# SCH_RightHalf_2022-04-16.net
KiCad netlist of a schematic drawn in EasyEDA
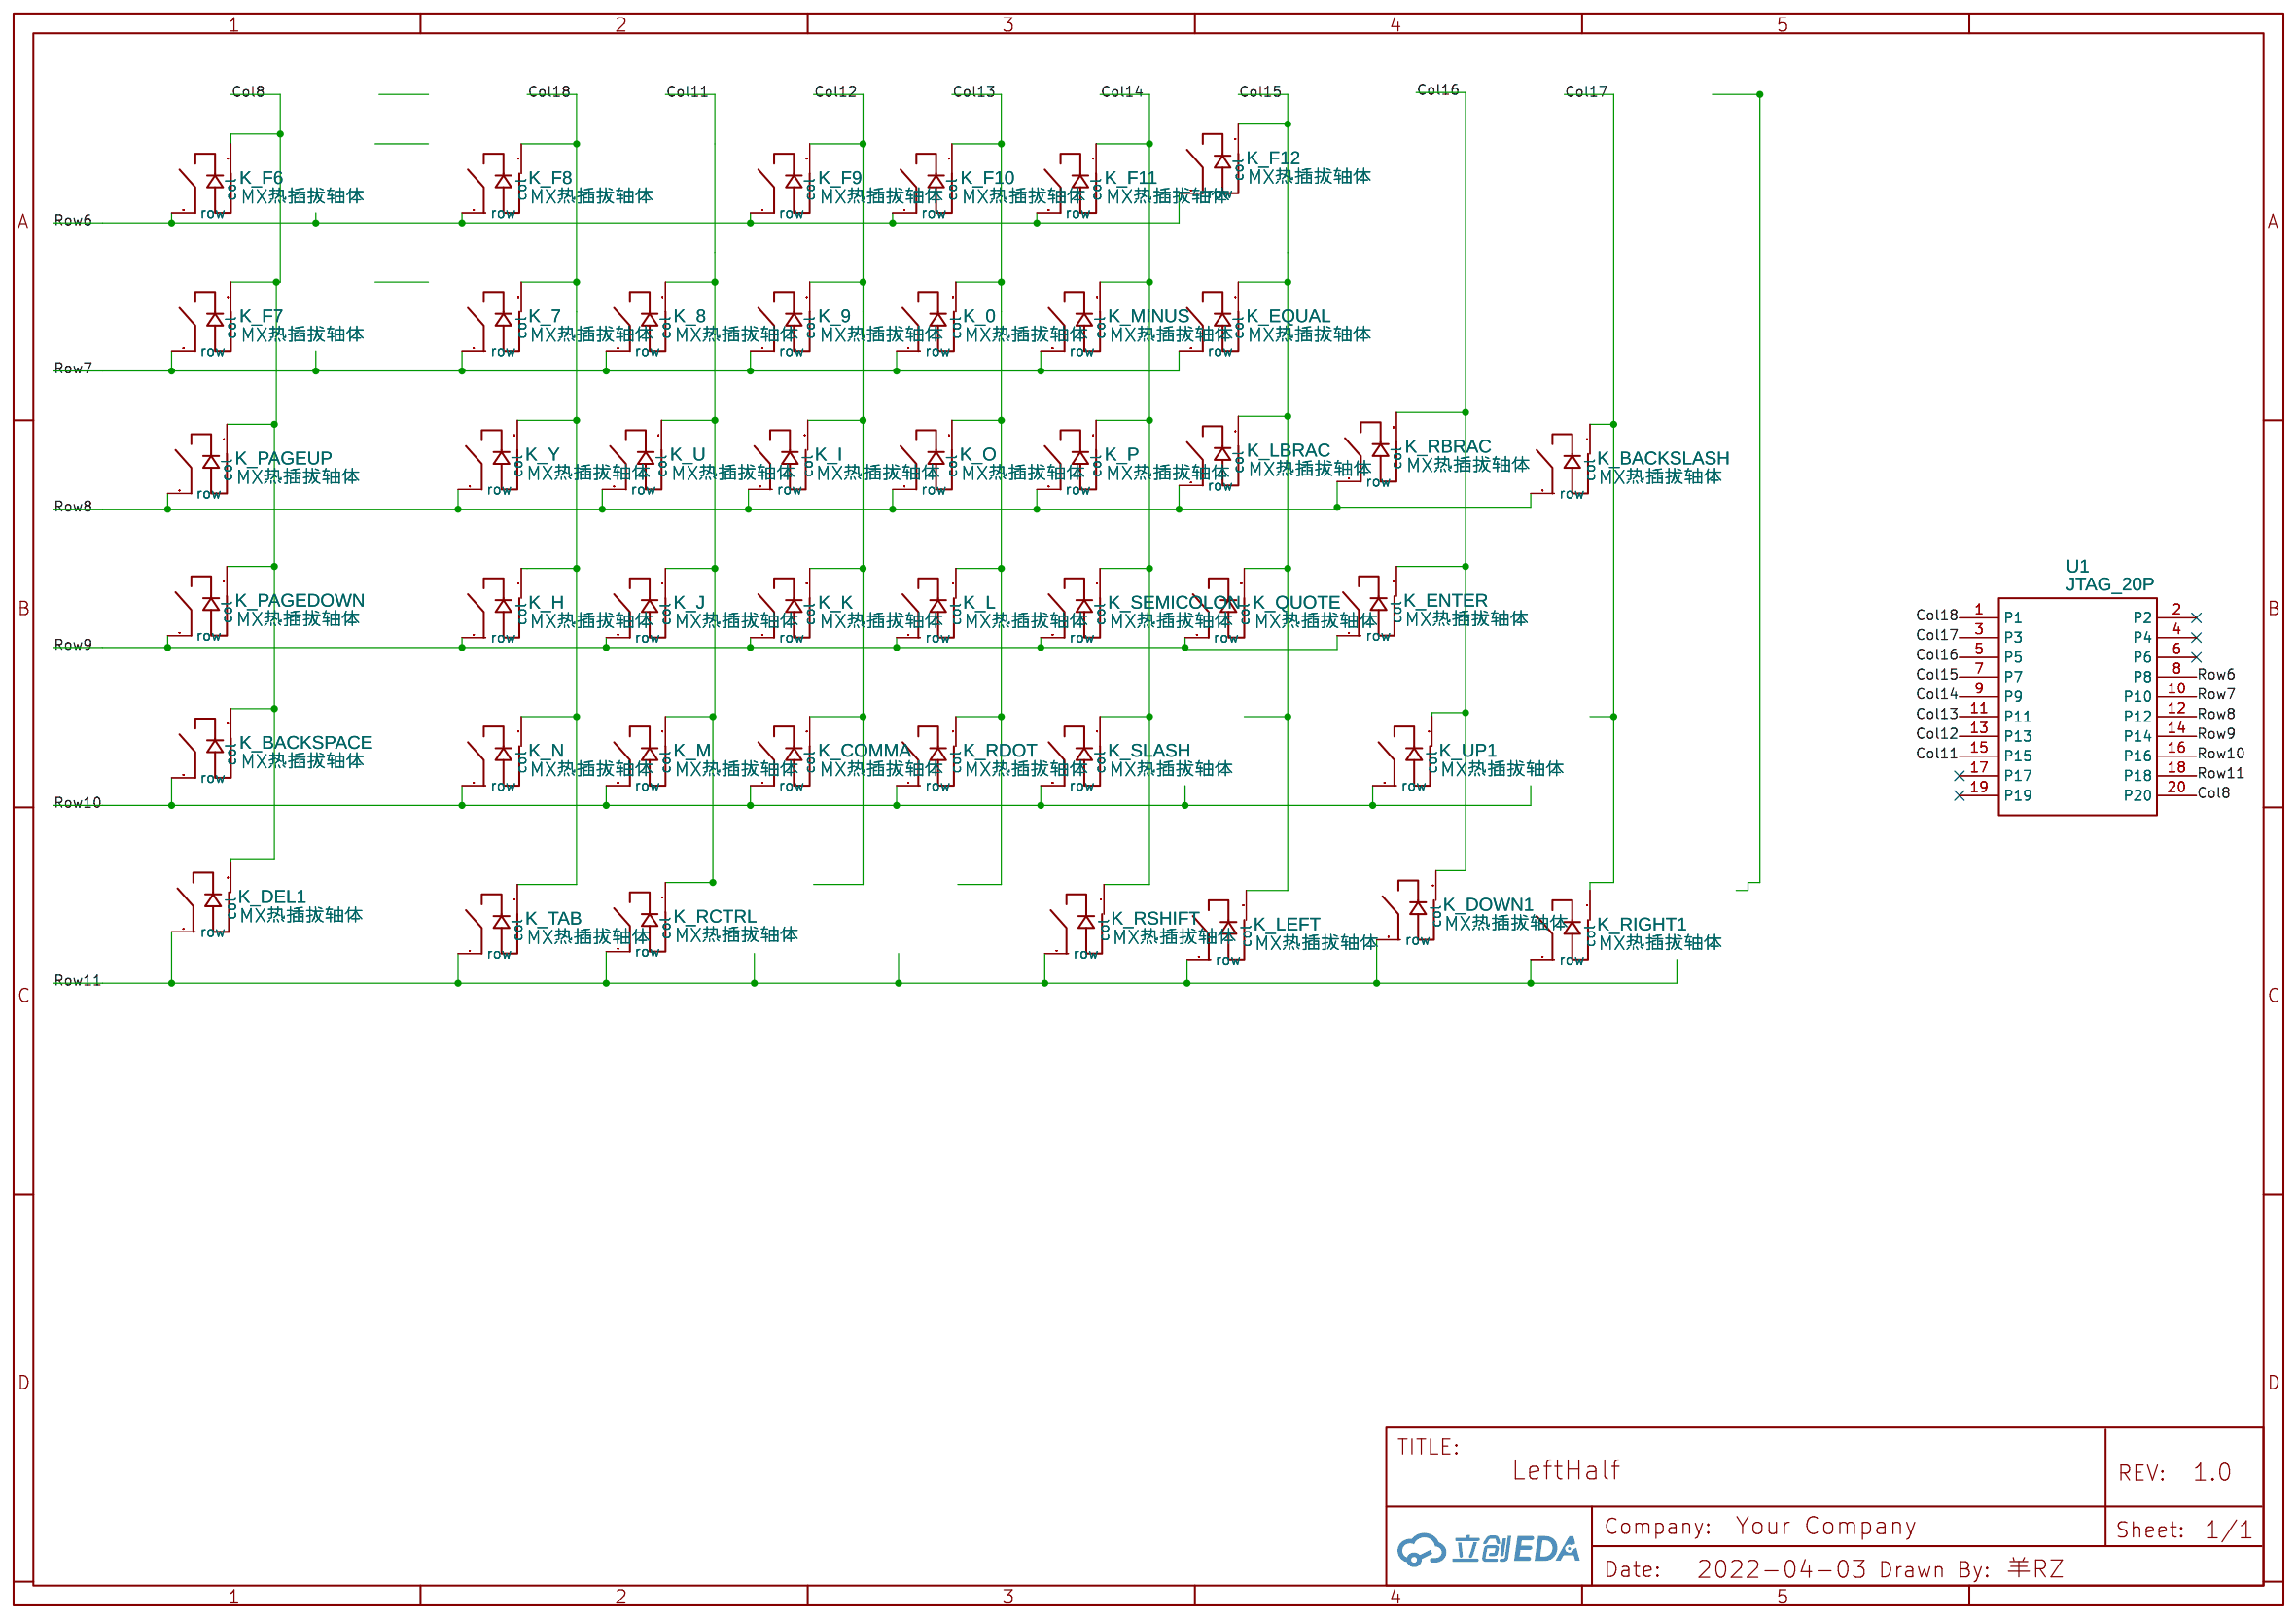
[diagram p0: schematic sheet]

(export (version "E")
  (design (tool "Eeschema 10.0.6"))
  (components
    (comp (ref "K_0") (value "MX热插拔轴体") (libsource (lib "") (part "MX热插拔轴体_19")))
    (comp (ref "K_7") (value "MX热插拔轴体") (libsource (lib "") (part "MX热插拔轴体_19")))
    (comp (ref "K_8") (value "MX热插拔轴体") (libsource (lib "") (part "MX热插拔轴体_2")))
    (comp (ref "K_9") (value "MX热插拔轴体") (libsource (lib "") (part "MX热插拔轴体_2")))
    (comp (ref "K_BACKSLASH") (value "MX热插拔轴体") (libsource (lib "") (part "MX热插拔轴体_10")))
    (comp (ref "K_BACKSPACE") (value "MX热插拔轴体") (libsource (lib "") (part "MX热插拔轴体_30")))
    (comp (ref "K_COMMA") (value "MX热插拔轴体") (libsource (lib "") (part "MX热插拔轴体_11")))
    (comp (ref "K_DEL1") (value "MX热插拔轴体") (libsource (lib "") (part "MX热插拔轴体_33")))
    (comp (ref "K_DOWN1") (value "MX热插拔轴体") (libsource (lib "") (part "MX热插拔轴体_32")))
    (comp (ref "K_ENTER") (value "MX热插拔轴体") (libsource (lib "") (part "MX热插拔轴体_26")))
    (comp (ref "K_EQUAL") (value "MX热插拔轴体") (libsource (lib "") (part "MX热插拔轴体_21")))
    (comp (ref "K_F6") (value "MX热插拔轴体") (libsource (lib "") (part "MX热插拔轴体_12")))
    (comp (ref "K_F7") (value "MX热插拔轴体") (libsource (lib "") (part "MX热插拔轴体_12")))
    (comp (ref "K_F8") (value "MX热插拔轴体") (libsource (lib "") (part "MX热插拔轴体_8")))
    (comp (ref "K_F9") (value "MX热插拔轴体") (libsource (lib "") (part "MX热插拔轴体_12")))
    (comp (ref "K_F10") (value "MX热插拔轴体") (libsource (lib "") (part "MX热插拔轴体_12")))
    (comp (ref "K_F11") (value "MX热插拔轴体") (libsource (lib "") (part "MX热插拔轴体_12")))
    (comp (ref "K_F12") (value "MX热插拔轴体") (libsource (lib "") (part "MX热插拔轴体_12")))
    (comp (ref "K_H") (value "MX热插拔轴体") (libsource (lib "") (part "MX热插拔轴体_27")))
    (comp (ref "K_I") (value "MX热插拔轴体") (libsource (lib "") (part "MX热插拔轴体_7")))
    (comp (ref "K_J") (value "MX热插拔轴体") (libsource (lib "") (part "MX热插拔轴体")))
    (comp (ref "K_K") (value "MX热插拔轴体") (libsource (lib "") (part "MX热插拔轴体_9")))
    (comp (ref "K_L") (value "MX热插拔轴体") (libsource (lib "") (part "MX热插拔轴体_35")))
    (comp (ref "K_LBRAC") (value "MX热插拔轴体") (libsource (lib "") (part "MX热插拔轴体_31")))
    (comp (ref "K_LEFT") (value "MX热插拔轴体") (libsource (lib "") (part "MX热插拔轴体_16")))
    (comp (ref "K_M") (value "MX热插拔轴体") (libsource (lib "") (part "MX热插拔轴体_34")))
    (comp (ref "K_MINUS") (value "MX热插拔轴体") (libsource (lib "") (part "MX热插拔轴体_25")))
    (comp (ref "K_N") (value "MX热插拔轴体") (libsource (lib "") (part "MX热插拔轴体_18")))
    (comp (ref "K_O") (value "MX热插拔轴体") (libsource (lib "") (part "MX热插拔轴体_36")))
    (comp (ref "K_P") (value "MX热插拔轴体") (libsource (lib "") (part "MX热插拔轴体_29")))
    (comp (ref "K_PAGEDOWN") (value "MX热插拔轴体") (libsource (lib "") (part "MX热插拔轴体_17")))
    (comp (ref "K_PAGEUP") (value "MX热插拔轴体") (libsource (lib "") (part "MX热插拔轴体_3")))
    (comp (ref "K_QUOTE") (value "MX热插拔轴体") (libsource (lib "") (part "MX热插拔轴体_22")))
    (comp (ref "K_RBRAC") (value "MX热插拔轴体") (libsource (lib "") (part "MX热插拔轴体_23")))
    (comp (ref "K_RCTRL") (value "MX热插拔轴体") (libsource (lib "") (part "MX热插拔轴体_14")))
    (comp (ref "K_RDOT") (value "MX热插拔轴体") (libsource (lib "") (part "MX热插拔轴体_20")))
    (comp (ref "K_RIGHT1") (value "MX热插拔轴体") (libsource (lib "") (part "MX热插拔轴体_4")))
    (comp (ref "K_RSHIFT") (value "MX热插拔轴体") (libsource (lib "") (part "MX热插拔轴体_5")))
    (comp (ref "K_SEMICOLON") (value "MX热插拔轴体") (libsource (lib "") (part "MX热插拔轴体_24")))
    (comp (ref "K_SLASH") (value "MX热插拔轴体") (libsource (lib "") (part "MX热插拔轴体_1")))
    (comp (ref "K_TAB") (value "MX热插拔轴体") (libsource (lib "") (part "MX热插拔轴体_6")))
    (comp (ref "K_U") (value "MX热插拔轴体") (libsource (lib "") (part "MX热插拔轴体_28")))
    (comp (ref "K_UP1") (value "MX热插拔轴体") (libsource (lib "") (part "MX热插拔轴体_15")))
    (comp (ref "K_Y") (value "MX热插拔轴体") (libsource (lib "") (part "MX热插拔轴体_13")))
    (comp (ref "U1") (value "JTAG_20P") (libsource (lib "") (part "JTAG_20P")))
  )
  (nets
    (net (code "1") (name "/Col8") (class "Default")
      (node (ref "K_BACKSPACE") (pin "COL") (pinfunction "col_COL") (pintype "unspecified"))
      (node (ref "K_DEL1") (pin "COL") (pinfunction "col_COL") (pintype "unspecified"))
      (node (ref "K_F6") (pin "COL") (pinfunction "col_COL") (pintype "unspecified"))
      (node (ref "K_F7") (pin "COL") (pinfunction "col_COL") (pintype "unspecified"))
      (node (ref "K_PAGEDOWN") (pin "COL") (pinfunction "col_COL") (pintype "unspecified"))
      (node (ref "K_PAGEUP") (pin "COL") (pinfunction "col_COL") (pintype "unspecified"))
      (node (ref "U1") (pin "20") (pinfunction "P20_20") (pintype "unspecified"))
    )
    (net (code "2") (name "/Col11") (class "Default")
      (node (ref "K_8") (pin "COL") (pinfunction "col_COL") (pintype "unspecified"))
      (node (ref "K_J") (pin "COL") (pinfunction "col_COL") (pintype "unspecified"))
      (node (ref "K_M") (pin "COL") (pinfunction "col_COL") (pintype "unspecified"))
      (node (ref "K_RCTRL") (pin "COL") (pinfunction "col_COL") (pintype "unspecified"))
      (node (ref "K_U") (pin "COL") (pinfunction "col_COL") (pintype "unspecified"))
      (node (ref "U1") (pin "15") (pinfunction "P15_15") (pintype "unspecified"))
    )
    (net (code "3") (name "/Col12") (class "Default")
      (node (ref "K_9") (pin "COL") (pinfunction "col_COL") (pintype "unspecified"))
      (node (ref "K_COMMA") (pin "COL") (pinfunction "col_COL") (pintype "unspecified"))
      (node (ref "K_F9") (pin "COL") (pinfunction "col_COL") (pintype "unspecified"))
      (node (ref "K_I") (pin "COL") (pinfunction "col_COL") (pintype "unspecified"))
      (node (ref "K_K") (pin "COL") (pinfunction "col_COL") (pintype "unspecified"))
      (node (ref "U1") (pin "13") (pinfunction "P13_13") (pintype "unspecified"))
    )
    (net (code "4") (name "/Col13") (class "Default")
      (node (ref "K_0") (pin "COL") (pinfunction "col_COL") (pintype "unspecified"))
      (node (ref "K_F10") (pin "COL") (pinfunction "col_COL") (pintype "unspecified"))
      (node (ref "K_L") (pin "COL") (pinfunction "col_COL") (pintype "unspecified"))
      (node (ref "K_O") (pin "COL") (pinfunction "col_COL") (pintype "unspecified"))
      (node (ref "K_RDOT") (pin "COL") (pinfunction "col_COL") (pintype "unspecified"))
      (node (ref "U1") (pin "11") (pinfunction "P11_11") (pintype "unspecified"))
    )
    (net (code "5") (name "/Col14") (class "Default")
      (node (ref "K_F11") (pin "COL") (pinfunction "col_COL") (pintype "unspecified"))
      (node (ref "K_MINUS") (pin "COL") (pinfunction "col_COL") (pintype "unspecified"))
      (node (ref "K_P") (pin "COL") (pinfunction "col_COL") (pintype "unspecified"))
      (node (ref "K_RSHIFT") (pin "COL") (pinfunction "col_COL") (pintype "unspecified"))
      (node (ref "K_SEMICOLON") (pin "COL") (pinfunction "col_COL") (pintype "unspecified"))
      (node (ref "K_SLASH") (pin "COL") (pinfunction "col_COL") (pintype "unspecified"))
      (node (ref "U1") (pin "9") (pinfunction "P9_9") (pintype "unspecified"))
    )
    (net (code "6") (name "/Col15") (class "Default")
      (node (ref "K_EQUAL") (pin "COL") (pinfunction "col_COL") (pintype "unspecified"))
      (node (ref "K_F12") (pin "COL") (pinfunction "col_COL") (pintype "unspecified"))
      (node (ref "K_LBRAC") (pin "COL") (pinfunction "col_COL") (pintype "unspecified"))
      (node (ref "K_LEFT") (pin "COL") (pinfunction "col_COL") (pintype "unspecified"))
      (node (ref "K_QUOTE") (pin "COL") (pinfunction "col_COL") (pintype "unspecified"))
      (node (ref "U1") (pin "7") (pinfunction "P7_7") (pintype "unspecified"))
    )
    (net (code "7") (name "/Col16") (class "Default")
      (node (ref "K_DOWN1") (pin "COL") (pinfunction "col_COL") (pintype "unspecified"))
      (node (ref "K_ENTER") (pin "COL") (pinfunction "col_COL") (pintype "unspecified"))
      (node (ref "K_RBRAC") (pin "COL") (pinfunction "col_COL") (pintype "unspecified"))
      (node (ref "K_UP1") (pin "COL") (pinfunction "col_COL") (pintype "unspecified"))
      (node (ref "U1") (pin "5") (pinfunction "P5_5") (pintype "unspecified"))
    )
    (net (code "8") (name "/Col17") (class "Default")
      (node (ref "K_BACKSLASH") (pin "COL") (pinfunction "col_COL") (pintype "unspecified"))
      (node (ref "K_RIGHT1") (pin "COL") (pinfunction "col_COL") (pintype "unspecified"))
      (node (ref "U1") (pin "3") (pinfunction "P3_3") (pintype "unspecified"))
    )
    (net (code "9") (name "/Col18") (class "Default")
      (node (ref "K_7") (pin "COL") (pinfunction "col_COL") (pintype "unspecified"))
      (node (ref "K_F8") (pin "COL") (pinfunction "col_COL") (pintype "unspecified"))
      (node (ref "K_H") (pin "COL") (pinfunction "col_COL") (pintype "unspecified"))
      (node (ref "K_N") (pin "COL") (pinfunction "col_COL") (pintype "unspecified"))
      (node (ref "K_TAB") (pin "COL") (pinfunction "col_COL") (pintype "unspecified"))
      (node (ref "K_Y") (pin "COL") (pinfunction "col_COL") (pintype "unspecified"))
      (node (ref "U1") (pin "1") (pinfunction "P1_1") (pintype "unspecified"))
    )
    (net (code "10") (name "/Row6") (class "Default")
      (node (ref "K_F10") (pin "ROW") (pinfunction "row_ROW") (pintype "unspecified"))
      (node (ref "K_F11") (pin "ROW") (pinfunction "row_ROW") (pintype "unspecified"))
      (node (ref "K_F12") (pin "ROW") (pinfunction "row_ROW") (pintype "unspecified"))
      (node (ref "K_F6") (pin "ROW") (pinfunction "row_ROW") (pintype "unspecified"))
      (node (ref "K_F8") (pin "ROW") (pinfunction "row_ROW") (pintype "unspecified"))
      (node (ref "K_F9") (pin "ROW") (pinfunction "row_ROW") (pintype "unspecified"))
      (node (ref "U1") (pin "8") (pinfunction "P8_8") (pintype "unspecified"))
    )
    (net (code "11") (name "/Row7") (class "Default")
      (node (ref "K_0") (pin "ROW") (pinfunction "row_ROW") (pintype "unspecified"))
      (node (ref "K_7") (pin "ROW") (pinfunction "row_ROW") (pintype "unspecified"))
      (node (ref "K_8") (pin "ROW") (pinfunction "row_ROW") (pintype "unspecified"))
      (node (ref "K_9") (pin "ROW") (pinfunction "row_ROW") (pintype "unspecified"))
      (node (ref "K_EQUAL") (pin "ROW") (pinfunction "row_ROW") (pintype "unspecified"))
      (node (ref "K_F7") (pin "ROW") (pinfunction "row_ROW") (pintype "unspecified"))
      (node (ref "K_MINUS") (pin "ROW") (pinfunction "row_ROW") (pintype "unspecified"))
      (node (ref "U1") (pin "10") (pinfunction "P10_10") (pintype "unspecified"))
    )
    (net (code "12") (name "/Row8") (class "Default")
      (node (ref "K_BACKSLASH") (pin "ROW") (pinfunction "row_ROW") (pintype "unspecified"))
      (node (ref "K_I") (pin "ROW") (pinfunction "row_ROW") (pintype "unspecified"))
      (node (ref "K_LBRAC") (pin "ROW") (pinfunction "row_ROW") (pintype "unspecified"))
      (node (ref "K_O") (pin "ROW") (pinfunction "row_ROW") (pintype "unspecified"))
      (node (ref "K_P") (pin "ROW") (pinfunction "row_ROW") (pintype "unspecified"))
      (node (ref "K_PAGEUP") (pin "ROW") (pinfunction "row_ROW") (pintype "unspecified"))
      (node (ref "K_RBRAC") (pin "ROW") (pinfunction "row_ROW") (pintype "unspecified"))
      (node (ref "K_U") (pin "ROW") (pinfunction "row_ROW") (pintype "unspecified"))
      (node (ref "K_Y") (pin "ROW") (pinfunction "row_ROW") (pintype "unspecified"))
      (node (ref "U1") (pin "12") (pinfunction "P12_12") (pintype "unspecified"))
    )
    (net (code "13") (name "/Row9") (class "Default")
      (node (ref "K_ENTER") (pin "ROW") (pinfunction "row_ROW") (pintype "unspecified"))
      (node (ref "K_H") (pin "ROW") (pinfunction "row_ROW") (pintype "unspecified"))
      (node (ref "K_J") (pin "ROW") (pinfunction "row_ROW") (pintype "unspecified"))
      (node (ref "K_K") (pin "ROW") (pinfunction "row_ROW") (pintype "unspecified"))
      (node (ref "K_L") (pin "ROW") (pinfunction "row_ROW") (pintype "unspecified"))
      (node (ref "K_PAGEDOWN") (pin "ROW") (pinfunction "row_ROW") (pintype "unspecified"))
      (node (ref "K_QUOTE") (pin "ROW") (pinfunction "row_ROW") (pintype "unspecified"))
      (node (ref "K_SEMICOLON") (pin "ROW") (pinfunction "row_ROW") (pintype "unspecified"))
      (node (ref "U1") (pin "14") (pinfunction "P14_14") (pintype "unspecified"))
    )
    (net (code "14") (name "/Row10") (class "Default")
      (node (ref "K_BACKSPACE") (pin "ROW") (pinfunction "row_ROW") (pintype "unspecified"))
      (node (ref "K_COMMA") (pin "ROW") (pinfunction "row_ROW") (pintype "unspecified"))
      (node (ref "K_M") (pin "ROW") (pinfunction "row_ROW") (pintype "unspecified"))
      (node (ref "K_N") (pin "ROW") (pinfunction "row_ROW") (pintype "unspecified"))
      (node (ref "K_RDOT") (pin "ROW") (pinfunction "row_ROW") (pintype "unspecified"))
      (node (ref "K_SLASH") (pin "ROW") (pinfunction "row_ROW") (pintype "unspecified"))
      (node (ref "K_UP1") (pin "ROW") (pinfunction "row_ROW") (pintype "unspecified"))
      (node (ref "U1") (pin "16") (pinfunction "P16_16") (pintype "unspecified"))
    )
    (net (code "15") (name "/Row11") (class "Default")
      (node (ref "K_DEL1") (pin "ROW") (pinfunction "row_ROW") (pintype "unspecified"))
      (node (ref "K_DOWN1") (pin "ROW") (pinfunction "row_ROW") (pintype "unspecified"))
      (node (ref "K_LEFT") (pin "ROW") (pinfunction "row_ROW") (pintype "unspecified"))
      (node (ref "K_RCTRL") (pin "ROW") (pinfunction "row_ROW") (pintype "unspecified"))
      (node (ref "K_RIGHT1") (pin "ROW") (pinfunction "row_ROW") (pintype "unspecified"))
      (node (ref "K_RSHIFT") (pin "ROW") (pinfunction "row_ROW") (pintype "unspecified"))
      (node (ref "K_TAB") (pin "ROW") (pinfunction "row_ROW") (pintype "unspecified"))
      (node (ref "U1") (pin "18") (pinfunction "P18_18") (pintype "unspecified"))
    )
    (net (code "16") (name "unconnected-(U1-P2-Pad2)") (class "Default")
      (node (ref "U1") (pin "2") (pinfunction "P2_2") (pintype "unspecified+no_connect"))
    )
    (net (code "17") (name "unconnected-(U1-P4-Pad4)") (class "Default")
      (node (ref "U1") (pin "4") (pinfunction "P4_4") (pintype "unspecified+no_connect"))
    )
    (net (code "18") (name "unconnected-(U1-P6-Pad6)") (class "Default")
      (node (ref "U1") (pin "6") (pinfunction "P6_6") (pintype "unspecified+no_connect"))
    )
    (net (code "19") (name "unconnected-(U1-P17-Pad17)") (class "Default")
      (node (ref "U1") (pin "17") (pinfunction "P17_17") (pintype "unspecified+no_connect"))
    )
    (net (code "20") (name "unconnected-(U1-P19-Pad19)") (class "Default")
      (node (ref "U1") (pin "19") (pinfunction "P19_19") (pintype "unspecified+no_connect"))
    )
  )
)
